# knobtesterB.net
KiCad netlist of a schematic drawn in EAGLE
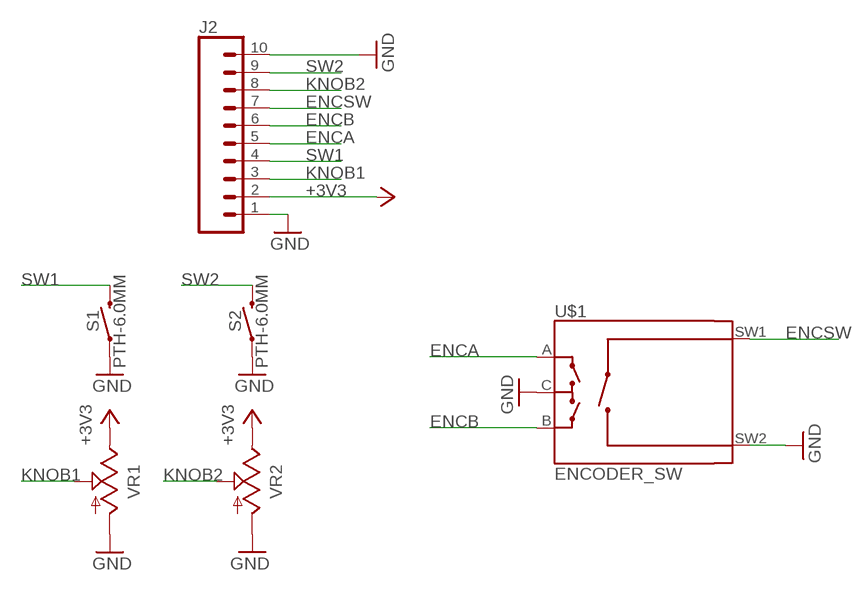
[diagram p0: schematic, sheet 1]

(export (version "E")
  (design (tool "Eeschema 10.0.6"))
  (components
    (comp (ref "J2")
      (value "CONN_10\"")
      (footprint "eagle-import:1X10")
      (libsource (lib "eagle-import") (part "CONN_10{dblquote}"))
    )
    (comp (ref "S1")
      (value "PTH-6.0MM")
      (footprint "eagle-import:TACTILE_SWITCH_PTH_6.0MM")
      (libsource (lib "eagle-import") (part "MOMENTARY-SWITCH-SPST-PTH-6.0MM"))
    )
    (comp (ref "S2")
      (value "PTH-6.0MM")
      (footprint "eagle-import:TACTILE_SWITCH_PTH_6.0MM")
      (libsource (lib "eagle-import") (part "MOMENTARY-SWITCH-SPST-PTH-6.0MM"))
    )
    (comp (ref "U$1")
      (value "ENCODER_SW")
      (footprint "eagle-import:ENCODER_SW")
      (libsource (lib "eagle-import") (part "ENCODER_SW"))
    )
    (comp (ref "VR1")
      (value "9MM_SNAP-IN_POT_")
      (footprint "eagle-import:9MM_SNAP-IN_POT")
      (libsource (lib "eagle-import") (part "9MM_SNAP-IN_POT_"))
    )
    (comp (ref "VR2")
      (value "9MM_SNAP-IN_POT_")
      (footprint "eagle-import:9MM_SNAP-IN_POT")
      (libsource (lib "eagle-import") (part "9MM_SNAP-IN_POT_"))
    )
  )
  (nets
    (net (code "1") (name "+3V3") (class "Default")
      (node (ref "J2") (pin "2") (pinfunction "2_2") (pintype "passive"))
      (node (ref "VR1") (pin "3") (pinfunction "E_3") (pintype "passive"))
      (node (ref "VR2") (pin "3") (pinfunction "E_3") (pintype "passive"))
    )
    (net (code "2") (name "/ENCA") (class "Default")
      (node (ref "J2") (pin "5") (pinfunction "5_5") (pintype "passive"))
      (node (ref "U$1") (pin "A") (pinfunction "A_A") (pintype "bidirectional"))
    )
    (net (code "3") (name "/ENCB") (class "Default")
      (node (ref "J2") (pin "6") (pinfunction "6_6") (pintype "passive"))
      (node (ref "U$1") (pin "B") (pinfunction "B_B") (pintype "bidirectional"))
    )
    (net (code "4") (name "/ENCSW") (class "Default")
      (node (ref "J2") (pin "7") (pinfunction "7_7") (pintype "passive"))
      (node (ref "U$1") (pin "SW1") (pinfunction "SW1_SW1") (pintype "passive"))
    )
    (net (code "5") (name "/KNOB1") (class "Default")
      (node (ref "J2") (pin "3") (pinfunction "3_3") (pintype "passive"))
      (node (ref "VR1") (pin "2") (pinfunction "S_2") (pintype "passive"))
    )
    (net (code "6") (name "/KNOB2") (class "Default")
      (node (ref "J2") (pin "8") (pinfunction "8_8") (pintype "passive"))
      (node (ref "VR2") (pin "2") (pinfunction "S_2") (pintype "passive"))
    )
    (net (code "7") (name "/SW1") (class "Default")
      (node (ref "J2") (pin "4") (pinfunction "4_4") (pintype "passive"))
      (node (ref "S1") (pin "3") (pinfunction "2_3") (pintype "passive"))
    )
    (net (code "8") (name "/SW2") (class "Default")
      (node (ref "J2") (pin "9") (pinfunction "9_9") (pintype "passive"))
      (node (ref "S2") (pin "3") (pinfunction "2_3") (pintype "passive"))
    )
    (net (code "9") (name "GND") (class "Default")
      (node (ref "J2") (pin "1") (pinfunction "1_1") (pintype "passive"))
      (node (ref "J2") (pin "10") (pinfunction "10_10") (pintype "passive"))
      (node (ref "S1") (pin "1") (pinfunction "1_1") (pintype "passive"))
      (node (ref "S2") (pin "1") (pinfunction "1_1") (pintype "passive"))
      (node (ref "U$1") (pin "C") (pinfunction "C_C") (pintype "bidirectional"))
      (node (ref "U$1") (pin "SW2") (pinfunction "SW2_SW2") (pintype "passive"))
      (node (ref "VR1") (pin "1") (pinfunction "A_1") (pintype "passive"))
      (node (ref "VR2") (pin "1") (pinfunction "A_1") (pintype "passive"))
    )
  )
)
